# Power.net
KiCad netlist of a schematic drawn in Altium Designer
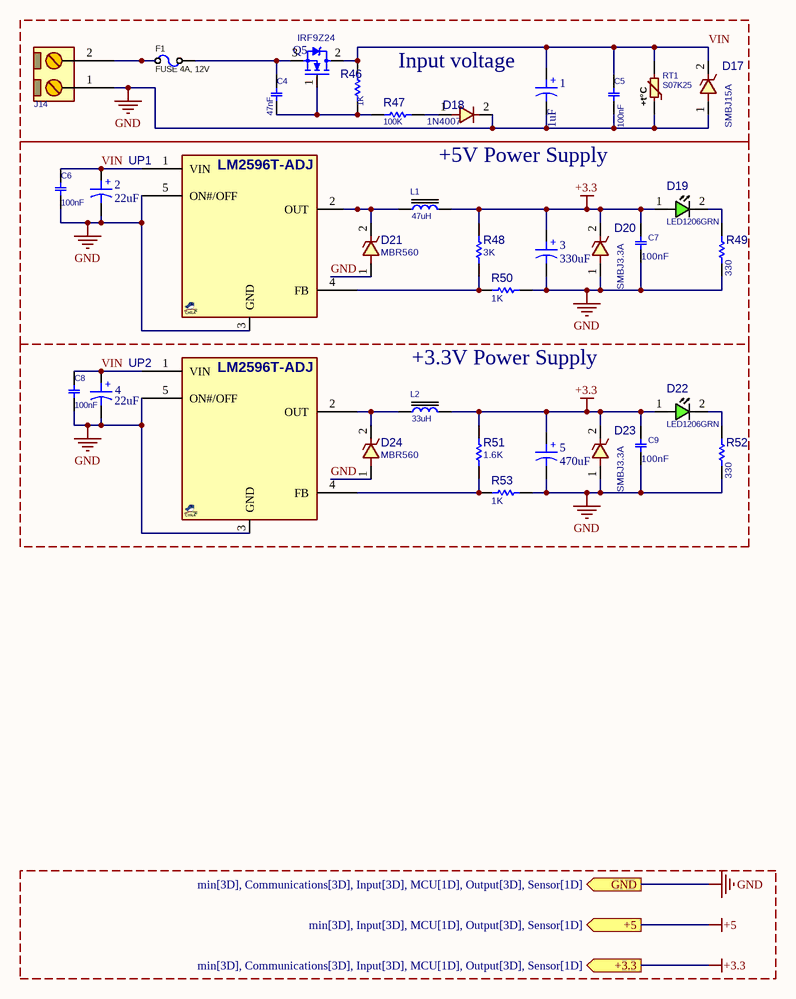
[diagram p0: Power.SchDoc]

(export (version "E")
  (design (tool "Eeschema 10.0.6"))
  (components
    (comp (ref "1")
      (value "1uF")
      (footprint "Cap electrolitic radial 10x20-5")
      (description "Cap electrolitic radial")
      (fields (field (name "DESIGNER") "Abbas Basereh"))
      (libsource (lib "Altium") (part "Cap electrolitic radial 10x21"))
    )
    (comp (ref "2")
      (value "22uF")
      (footprint "Cap electrolitic radial 10x20-5")
      (description "Cap electrolitic radial")
      (fields (field (name "DESIGNER") "Abbas Basereh"))
      (libsource (lib "Altium") (part "Cap electrolitic radial 10x21"))
    )
    (comp (ref "3")
      (value "330uF")
      (footprint "Cap electrolitic radial 10x20-5")
      (description "Cap electrolitic radial")
      (fields (field (name "DESIGNER") "Abbas Basereh"))
      (libsource (lib "Altium") (part "Cap electrolitic radial 10x21"))
    )
    (comp (ref "4")
      (value "22uF")
      (footprint "Cap electrolitic radial 10x20-5")
      (description "Cap electrolitic radial")
      (fields (field (name "DESIGNER") "Abbas Basereh"))
      (libsource (lib "Altium") (part "Cap electrolitic radial 10x21"))
    )
    (comp (ref "5")
      (value "470uF")
      (footprint "Cap electrolitic radial 10x20-5")
      (description "Cap electrolitic radial")
      (fields (field (name "DESIGNER") "Abbas Basereh"))
      (libsource (lib "Altium") (part "Cap electrolitic radial 10x21"))
    )
    (comp (ref "C4")
      (value "47nF")
      (footprint "C_CERM_D3")
      (description "CAP, THD, CER MULTI LAYER,")
      (fields (field (name "MANF_P#") "MANF_PART#") (field (name "MANF") "MANF"))
      (libsource (lib "passive_thd") (part "CAP_THD_CER"))
    )
    (comp (ref "C5")
      (value "100nF")
      (footprint "C_CERM_D3")
      (description "CAP, THD, CER MULTI LAYER,")
      (fields (field (name "MANF_P#") "MANF_PART#") (field (name "MANF") "MANF"))
      (libsource (lib "passive_thd") (part "CAP_THD_CER"))
    )
    (comp (ref "C6")
      (value "100nF")
      (footprint "C_CERM_D3")
      (description "CAP, THD, CER MULTI LAYER,")
      (fields (field (name "MANF_P#") "MANF_PART#") (field (name "MANF") "MANF"))
      (libsource (lib "passive_thd") (part "CAP_THD_CER"))
    )
    (comp (ref "C7")
      (value "100nF")
      (footprint "C1206")
      (description "CAP, MLCC")
      (fields (field (name "MANF_P#") "MANF_PART#") (field (name "MANF") "Murata"))
      (libsource (lib "passive_smd") (part "CAP_SMD_MLCC"))
    )
    (comp (ref "C8")
      (value "100nF")
      (footprint "C_CERM_D3")
      (description "CAP, THD, CER MULTI LAYER,")
      (fields (field (name "MANF_P#") "MANF_PART#") (field (name "MANF") "MANF"))
      (libsource (lib "passive_thd") (part "CAP_THD_CER"))
    )
    (comp (ref "C9")
      (value "100nF")
      (footprint "C1206")
      (description "CAP, MLCC")
      (fields (field (name "MANF_P#") "MANF_PART#") (field (name "MANF") "Murata"))
      (libsource (lib "passive_smd") (part "CAP_SMD_MLCC"))
    )
    (comp (ref "D17")
      (value "SMBJ15A")
      (footprint "D_SMB")
      (description "DIODE, ZENER, 2W, 36V")
      (fields (field (name "MANF") "Diotec") (field (name "MANF_P#") "Z2SMB36"))
      (libsource (lib "diode") (part "DIODE_SMD_ZENER_Z2SMB36"))
    )
    (comp (ref "D18")
      (value "1N4007")
      (footprint "D_AX03_1WS")
      (description "DIODE, GENERAL PURPOSE, 1000V/1A")
      (fields (field (name "MANF") "Diodes"))
      (libsource (lib "diode") (part "DIODE_THD_1N4007"))
    )
    (comp (ref "D19")
      (value "LED1206GRN")
      (footprint "LED1206GRN")
      (description "LED, SMD, 1206, GREEN")
      (libsource (lib "led(diode)") (part "LED_SMD_1206_GRN"))
    )
    (comp (ref "D20")
      (value "SMBJ3.3A")
      (footprint "D_SMB")
      (description "DIODE, ZENER, 2W, 36V")
      (fields (field (name "MANF") "Diotec") (field (name "MANF_P#") "Z2SMB36"))
      (libsource (lib "diode") (part "DIODE_SMD_ZENER_Z2SMB36"))
    )
    (comp (ref "D21")
      (value "MBR560")
      (footprint "D_AX04_DO41")
      (description "DIODE, ZENER, 0.2W, 15V")
      (fields (field (name "MANF") "Diodes") (field (name "MANF_P#") "ZENER15V"))
      (libsource (lib "diode") (part "DIODE_THD_ZENER"))
    )
    (comp (ref "D22")
      (value "LED1206GRN")
      (footprint "LED1206GRN")
      (description "LED, SMD, 1206, GREEN")
      (libsource (lib "led(diode)") (part "LED_SMD_1206_GRN"))
    )
    (comp (ref "D23")
      (value "SMBJ3.3A")
      (footprint "D_SMB")
      (description "DIODE, ZENER, 2W, 36V")
      (fields (field (name "MANF") "Diotec") (field (name "MANF_P#") "Z2SMB36"))
      (libsource (lib "diode") (part "DIODE_SMD_ZENER_Z2SMB36"))
    )
    (comp (ref "D24")
      (value "MBR560")
      (footprint "D_AX04_DO41")
      (description "DIODE, ZENER, 0.2W, 15V")
      (fields (field (name "MANF") "Diodes") (field (name "MANF_P#") "ZENER15V"))
      (libsource (lib "diode") (part "DIODE_THD_ZENER"))
    )
    (comp (ref "F1")
      (value "FUSE 4A, 12V")
      (footprint "FUSH_6X32MM_4PIN")
      (description "Fuse HOLDER 5X20")
      (fields (field (name "MANF") "MANF") (field (name "MANF_P#") "MANF_PART#"))
      (libsource (lib "altium-import") (part "root_0_FUSE_6X32_"))
    )
    (comp (ref "J14")
      (value "CONN_TB2")
      (footprint "TBB_2")
      (description "CONN, TERMINAL BLOCK, 5.08mm pitch")
      (libsource (lib "conn_terminalB") (part "CONN_TB2"))
    )
    (comp (ref "L1")
      (value "47uH")
      (footprint "L_7")
      (description "INDUCTOR, 10uH 2A, 38mOhm, 2626")
      (fields (field (name "MANF_P#") "SRR6038-100Y") (field (name "MANF") "Bourns"))
      (libsource (lib "altium-import") (part "root_0_IND_SMD_10uH_2A_"))
    )
    (comp (ref "L2")
      (value "33uH")
      (footprint "L_7")
      (description "INDUCTOR, 10uH 2A, 38mOhm, 2626")
      (fields (field (name "MANF_P#") "SRR6038-100Y") (field (name "MANF") "Bourns"))
      (libsource (lib "altium-import") (part "root_0_IND_SMD_10uH_2A_"))
    )
    (comp (ref "Q5")
      (value "IRF9Z24")
      (footprint "TO247_3")
      (fields (field (name "MANF_P#") "IRFP"))
      (libsource (lib "altium-import") (part "root_1_mirrored_MOSN_IRFP_"))
    )
    (comp (ref "R46")
      (value "1K")
      (footprint "R0125W_AX03")
      (description "RESISTOR, THD")
      (fields (field (name "MANF_P#") "RK73H1ETTP4701F") (field (name "MANF") "KOA SPEER"))
      (libsource (lib "passive_thd") (part "RES_THD"))
    )
    (comp (ref "R47")
      (value "100K")
      (footprint "R0125W_AX03")
      (description "RESISTOR, THD")
      (fields (field (name "MANF_P#") "RK73H1ETTP4701F") (field (name "MANF") "KOA SPEER"))
      (libsource (lib "passive_thd") (part "RES_THD"))
    )
    (comp (ref "R48")
      (value "3K")
      (footprint "R1206")
      (description "RESISTOR, SMD")
      (libsource (lib "passive_smd") (part "RES_SMD"))
    )
    (comp (ref "R49")
      (value "330")
      (footprint "R1206")
      (description "RESISTOR, SMD")
      (libsource (lib "passive_smd") (part "RES_SMD"))
    )
    (comp (ref "R50")
      (value "1K")
      (footprint "R1206")
      (description "RESISTOR, SMD")
      (libsource (lib "passive_smd") (part "RES_SMD"))
    )
    (comp (ref "R51")
      (value "1.6K")
      (footprint "R1206")
      (description "RESISTOR, SMD")
      (libsource (lib "passive_smd") (part "RES_SMD"))
    )
    (comp (ref "R52")
      (value "330")
      (footprint "R1206")
      (description "RESISTOR, SMD")
      (libsource (lib "passive_smd") (part "RES_SMD"))
    )
    (comp (ref "R53")
      (value "1K")
      (footprint "R1206")
      (description "RESISTOR, SMD")
      (libsource (lib "passive_smd") (part "RES_SMD"))
    )
    (comp (ref "RT1")
      (value "S07K25")
      (footprint "NTC_15X6")
      (description "Thermistor, NTC")
      (fields (field (name "MANF_P#") "PTC"))
      (libsource (lib "altium-import") (part "root_1_PTC10K_"))
    )
    (comp (ref "UP1")
      (value "LM2596T-ADJ")
      (footprint "TO220_5")
      (description "REG, Switching, Buck, 3A, ADJ, 150KHz, TO-220")
      (fields (field (name "MANF") "TI, ON, TS"))
      (libsource (lib "altium-import") (part "root_0_VREG_LM2596T-ADJ_TO220_"))
    )
    (comp (ref "UP2")
      (value "LM2596T-ADJ")
      (footprint "TO220_5")
      (description "REG, Switching, Buck, 3A, ADJ, 150KHz, TO-220")
      (fields (field (name "MANF") "TI, ON, TS"))
      (libsource (lib "altium-import") (part "root_0_VREG_LM2596T-ADJ_TO220_"))
    )
  )
  (nets
    (net (code "1") (name "+3.3") (class "Default")
      (node (ref "3") (pin "1") (pinfunction "1_1") (pintype "passive"))
      (node (ref "5") (pin "1") (pinfunction "1_1") (pintype "passive"))
      (node (ref "C7") (pin "1") (pinfunction "1_1") (pintype "passive"))
      (node (ref "C9") (pin "1") (pinfunction "1_1") (pintype "passive"))
      (node (ref "D19") (pin "1") (pinfunction "ANODE_1") (pintype "passive"))
      (node (ref "D20") (pin "2") (pinfunction "2_2") (pintype "passive"))
      (node (ref "D22") (pin "1") (pinfunction "ANODE_1") (pintype "passive"))
      (node (ref "D23") (pin "2") (pinfunction "2_2") (pintype "passive"))
      (node (ref "L1") (pin "2") (pinfunction "2_2") (pintype "passive"))
      (node (ref "L2") (pin "2") (pinfunction "2_2") (pintype "passive"))
      (node (ref "R48") (pin "1") (pinfunction "1_1") (pintype "passive"))
      (node (ref "R51") (pin "2") (pinfunction "2_2") (pintype "passive"))
    )
    (net (code "3") (name "/VIN") (class "Default")
      (node (ref "1") (pin "1") (pinfunction "1_1") (pintype "passive"))
      (node (ref "2") (pin "1") (pinfunction "1_1") (pintype "passive"))
      (node (ref "4") (pin "1") (pinfunction "1_1") (pintype "passive"))
      (node (ref "C5") (pin "2") (pinfunction "2_2") (pintype "passive"))
      (node (ref "C6") (pin "2") (pinfunction "2_2") (pintype "passive"))
      (node (ref "C8") (pin "2") (pinfunction "2_2") (pintype "passive"))
      (node (ref "D17") (pin "2") (pinfunction "2_2") (pintype "passive"))
      (node (ref "Q5") (pin "2") (pinfunction "D_2") (pintype "passive"))
      (node (ref "R46") (pin "2") (pinfunction "2_2") (pintype "passive"))
      (node (ref "RT1") (pin "2") (pinfunction "2_2") (pintype "passive"))
      (node (ref "UP1") (pin "1") (pinfunction "VIN_1") (pintype "power_in"))
      (node (ref "UP2") (pin "1") (pinfunction "VIN_1") (pintype "power_in"))
    )
    (net (code "4") (name "GND") (class "Default")
      (node (ref "1") (pin "2") (pinfunction "2_2") (pintype "passive"))
      (node (ref "2") (pin "2") (pinfunction "2_2") (pintype "passive"))
      (node (ref "3") (pin "2") (pinfunction "2_2") (pintype "passive"))
      (node (ref "4") (pin "2") (pinfunction "2_2") (pintype "passive"))
      (node (ref "5") (pin "2") (pinfunction "2_2") (pintype "passive"))
      (node (ref "C5") (pin "1") (pinfunction "1_1") (pintype "passive"))
      (node (ref "C6") (pin "1") (pinfunction "1_1") (pintype "passive"))
      (node (ref "C7") (pin "2") (pinfunction "2_2") (pintype "passive"))
      (node (ref "C8") (pin "1") (pinfunction "1_1") (pintype "passive"))
      (node (ref "C9") (pin "2") (pinfunction "2_2") (pintype "passive"))
      (node (ref "D17") (pin "1") (pinfunction "1_1") (pintype "passive"))
      (node (ref "D18") (pin "2") (pinfunction "2_2") (pintype "passive"))
      (node (ref "D20") (pin "1") (pinfunction "1_1") (pintype "passive"))
      (node (ref "D21") (pin "1") (pinfunction "1_1") (pintype "passive"))
      (node (ref "D23") (pin "1") (pinfunction "1_1") (pintype "passive"))
      (node (ref "D24") (pin "1") (pinfunction "1_1") (pintype "passive"))
      (node (ref "J14") (pin "1") (pinfunction "1_1") (pintype "passive"))
      (node (ref "R49") (pin "2") (pinfunction "2_2") (pintype "passive"))
      (node (ref "R50") (pin "2") (pinfunction "2_2") (pintype "passive"))
      (node (ref "R52") (pin "2") (pinfunction "2_2") (pintype "passive"))
      (node (ref "R53") (pin "2") (pinfunction "2_2") (pintype "passive"))
      (node (ref "RT1") (pin "1") (pinfunction "1_1") (pintype "passive"))
      (node (ref "UP1") (pin "3") (pinfunction "GND_3") (pintype "power_in"))
      (node (ref "UP1") (pin "5") (pinfunction "ON#/OFF_5") (pintype "passive"))
      (node (ref "UP2") (pin "3") (pinfunction "GND_3") (pintype "power_in"))
      (node (ref "UP2") (pin "5") (pinfunction "ON#/OFF_5") (pintype "passive"))
    )
    (net (code "5") (name "Net-(D18-Pad1)") (class "Default")
      (node (ref "D18") (pin "1") (pinfunction "1_1") (pintype "passive"))
      (node (ref "R47") (pin "2") (pinfunction "2_2") (pintype "passive"))
    )
    (net (code "6") (name "Net-(D19-CATHODE)") (class "Default")
      (node (ref "D19") (pin "2") (pinfunction "CATHODE_2") (pintype "passive"))
      (node (ref "R49") (pin "1") (pinfunction "1_1") (pintype "passive"))
    )
    (net (code "7") (name "Net-(D22-CATHODE)") (class "Default")
      (node (ref "D22") (pin "2") (pinfunction "CATHODE_2") (pintype "passive"))
      (node (ref "R52") (pin "1") (pinfunction "1_1") (pintype "passive"))
    )
    (net (code "8") (name "Net-(F1-Pad1)") (class "Default")
      (node (ref "F1") (pin "1") (pinfunction "1_1") (pintype "passive"))
      (node (ref "J14") (pin "2") (pinfunction "2_2") (pintype "passive"))
    )
    (net (code "9") (name "Net-(Q5-G)") (class "Default")
      (node (ref "C4") (pin "1") (pinfunction "1_1") (pintype "passive"))
      (node (ref "Q5") (pin "1") (pinfunction "G_1") (pintype "passive"))
      (node (ref "R46") (pin "1") (pinfunction "1_1") (pintype "passive"))
      (node (ref "R47") (pin "1") (pinfunction "1_1") (pintype "passive"))
    )
    (net (code "10") (name "Net-(Q5-S)") (class "Default")
      (node (ref "C4") (pin "2") (pinfunction "2_2") (pintype "passive"))
      (node (ref "F1") (pin "2") (pinfunction "2_2") (pintype "passive"))
      (node (ref "Q5") (pin "3") (pinfunction "S_3") (pintype "passive"))
    )
    (net (code "11") (name "Net-(UP1-FB)") (class "Default")
      (node (ref "R48") (pin "2") (pinfunction "2_2") (pintype "passive"))
      (node (ref "R50") (pin "1") (pinfunction "1_1") (pintype "passive"))
      (node (ref "UP1") (pin "4") (pinfunction "FB_4") (pintype "passive"))
    )
    (net (code "12") (name "Net-(UP1-OUT)") (class "Default")
      (node (ref "D21") (pin "2") (pinfunction "2_2") (pintype "passive"))
      (node (ref "L1") (pin "1") (pinfunction "1_1") (pintype "passive"))
      (node (ref "UP1") (pin "2") (pinfunction "OUT_2") (pintype "power_in"))
    )
    (net (code "13") (name "Net-(UP2-FB)") (class "Default")
      (node (ref "R51") (pin "1") (pinfunction "1_1") (pintype "passive"))
      (node (ref "R53") (pin "1") (pinfunction "1_1") (pintype "passive"))
      (node (ref "UP2") (pin "4") (pinfunction "FB_4") (pintype "passive"))
    )
    (net (code "14") (name "Net-(UP2-OUT)") (class "Default")
      (node (ref "D24") (pin "2") (pinfunction "2_2") (pintype "passive"))
      (node (ref "L2") (pin "1") (pinfunction "1_1") (pintype "passive"))
      (node (ref "UP2") (pin "2") (pinfunction "OUT_2") (pintype "power_in"))
    )
  )
)
